# SterownikDriver_01.net
KiCad netlist of a schematic drawn in EAGLE
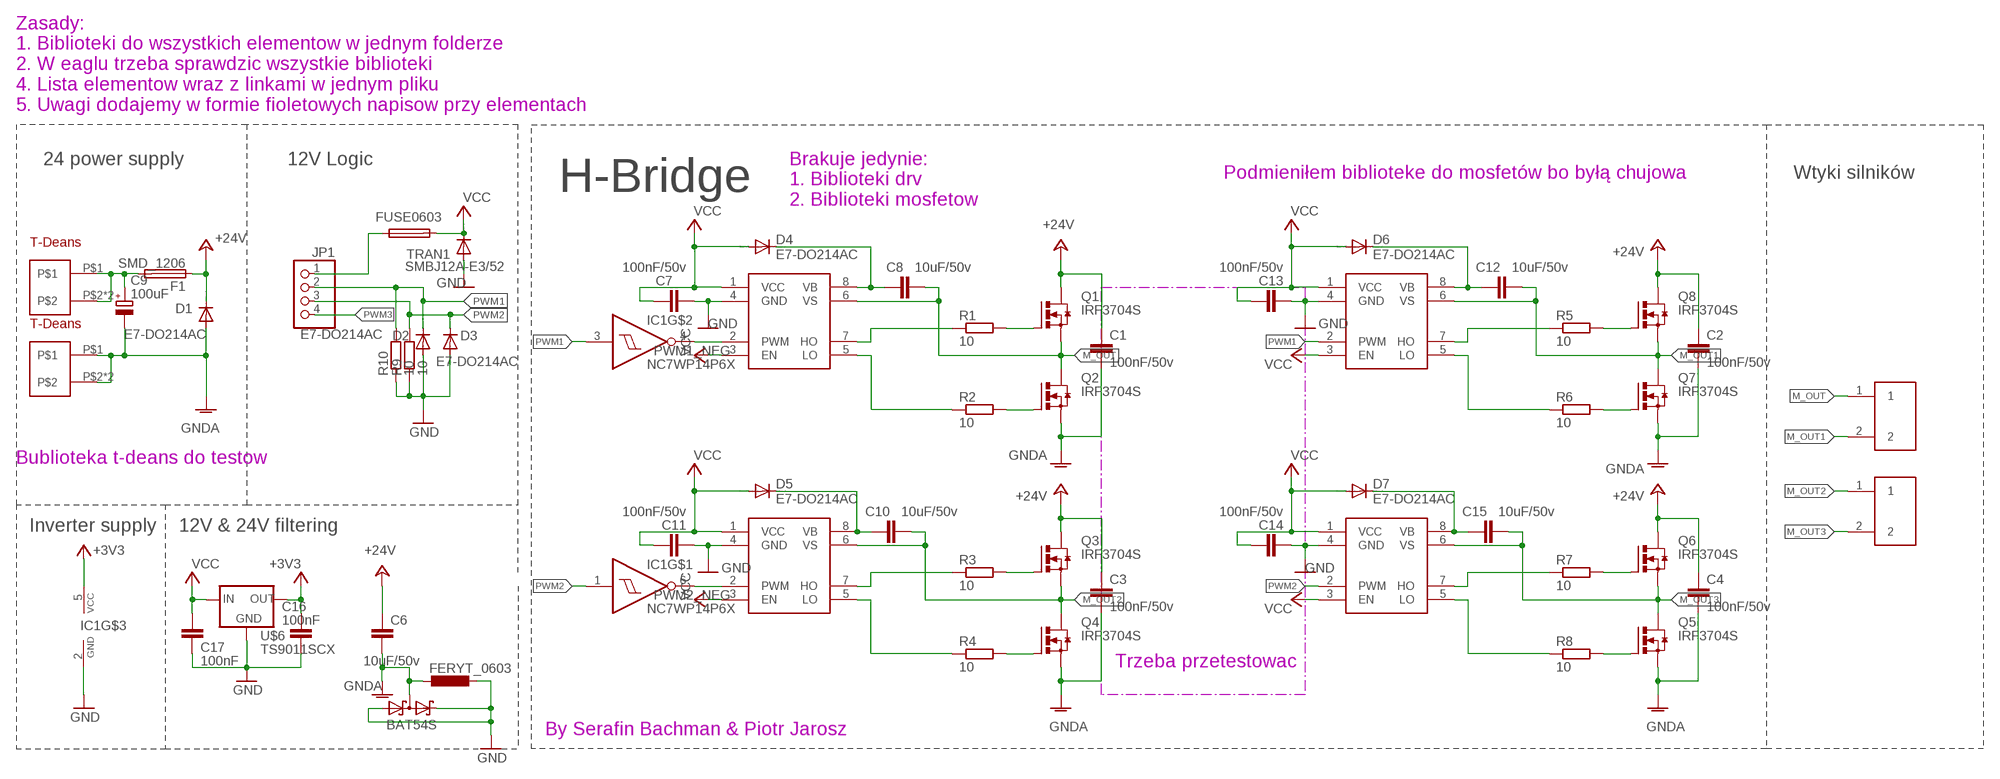
[diagram p0: schematic, sheet 1]

(export (version "E")
  (design (tool "Eeschema 10.0.6"))
  (components
    (comp (ref "C1")
      (value "100nF/50v")
      (footprint "eagle-import:C0603K")
      (libsource (lib "eagle-import") (part "C-EUC0603K"))
    )
    (comp (ref "C2")
      (value "100nF/50v")
      (footprint "eagle-import:C0603K")
      (libsource (lib "eagle-import") (part "C-EUC0603K"))
    )
    (comp (ref "C3")
      (value "100nF/50v")
      (footprint "eagle-import:C0603K")
      (libsource (lib "eagle-import") (part "C-EUC0603K"))
    )
    (comp (ref "C4")
      (value "100nF/50v")
      (footprint "eagle-import:C0603K")
      (libsource (lib "eagle-import") (part "C-EUC0603K"))
    )
    (comp (ref "C6")
      (value "10uF/50v")
      (footprint "eagle-import:C0603K")
      (libsource (lib "eagle-import") (part "C-EUC0603K"))
    )
    (comp (ref "C7")
      (value "100nF/50v")
      (footprint "eagle-import:C0603K")
      (libsource (lib "eagle-import") (part "C-EUC0603K"))
    )
    (comp (ref "C8")
      (value "10uF/50v")
      (footprint "eagle-import:C0603K")
      (libsource (lib "eagle-import") (part "C-EUC0603K"))
    )
    (comp (ref "C9")
      (value "100uF")
      (footprint "eagle-import:140CLH-0810")
      (libsource (lib "eagle-import") (part "CPOL-EU140CLH-0810"))
    )
    (comp (ref "C10")
      (value "10uF/50v")
      (footprint "eagle-import:C0603K")
      (libsource (lib "eagle-import") (part "C-EUC0603K"))
    )
    (comp (ref "C11")
      (value "100nF/50v")
      (footprint "eagle-import:C0603K")
      (libsource (lib "eagle-import") (part "C-EUC0603K"))
    )
    (comp (ref "C12")
      (value "10uF/50v")
      (footprint "eagle-import:C0603K")
      (libsource (lib "eagle-import") (part "C-EUC0603K"))
    )
    (comp (ref "C13")
      (value "100nF/50v")
      (footprint "eagle-import:C0603K")
      (libsource (lib "eagle-import") (part "C-EUC0603K"))
    )
    (comp (ref "C14")
      (value "100nF/50v")
      (footprint "eagle-import:C0603K")
      (libsource (lib "eagle-import") (part "C-EUC0603K"))
    )
    (comp (ref "C15")
      (value "10uF/50v")
      (footprint "eagle-import:C0603K")
      (libsource (lib "eagle-import") (part "C-EUC0603K"))
    )
    (comp (ref "C16")
      (value "100nF")
      (footprint "eagle-import:C0603K")
      (libsource (lib "eagle-import") (part "C-EUC0603K"))
    )
    (comp (ref "C17")
      (value "100nF")
      (footprint "eagle-import:C0603K")
      (libsource (lib "eagle-import") (part "C-EUC0603K"))
    )
    (comp (ref "D1")
      (value "E7-DO214AC")
      (footprint "eagle-import:DO214AC")
      (libsource (lib "eagle-import") (part "E7-DO214AC"))
    )
    (comp (ref "D2")
      (value "E7-DO214AC")
      (footprint "eagle-import:DO214AC")
      (libsource (lib "eagle-import") (part "E7-DO214AC"))
    )
    (comp (ref "D3")
      (value "E7-DO214AC")
      (footprint "eagle-import:DO214AC")
      (libsource (lib "eagle-import") (part "E7-DO214AC"))
    )
    (comp (ref "D4")
      (value "E7-DO214AC")
      (footprint "eagle-import:DO214AC")
      (libsource (lib "eagle-import") (part "E7-DO214AC"))
    )
    (comp (ref "D5")
      (value "E7-DO214AC")
      (footprint "eagle-import:DO214AC")
      (libsource (lib "eagle-import") (part "E7-DO214AC"))
    )
    (comp (ref "D6")
      (value "E7-DO214AC")
      (footprint "eagle-import:DO214AC")
      (libsource (lib "eagle-import") (part "E7-DO214AC"))
    )
    (comp (ref "D7")
      (value "E7-DO214AC")
      (footprint "eagle-import:DO214AC")
      (libsource (lib "eagle-import") (part "E7-DO214AC"))
    )
    (comp (ref "D8")
      (value "BAT54S")
      (footprint "eagle-import:SOT23")
      (libsource (lib "eagle-import") (part "BAT54S"))
    )
    (comp (ref "F1")
      (value "SMD_1206")
      (footprint "eagle-import:1026")
      (libsource (lib "eagle-import") (part "SMD_1206"))
    )
    (comp (ref "GND")
      (value "T-DEANS")
      (footprint "eagle-import:T-DEANS")
      (libsource (lib "eagle-import") (part "T-DEANS"))
    )
    (comp (ref "IC1")
      (value "NC7WP14P6X")
      (footprint "eagle-import:SOT65P210X110-6AN_SC88_SC70-6")
      (libsource (lib "eagle-import") (part "NC7W14P6XP"))
    )
    (comp (ref "JP1")
      (value "PINHD-1X4")
      (footprint "eagle-import:1X04")
      (libsource (lib "eagle-import") (part "PINHD-1X4"))
    )
    (comp (ref "Q1")
      (value "IRF3704S")
      (footprint "eagle-import:D2PACK")
      (libsource (lib "eagle-import") (part "IRF3704S"))
    )
    (comp (ref "Q2")
      (value "IRF3704S")
      (footprint "eagle-import:D2PACK")
      (libsource (lib "eagle-import") (part "IRF3704S"))
    )
    (comp (ref "Q3")
      (value "IRF3704S")
      (footprint "eagle-import:D2PACK")
      (libsource (lib "eagle-import") (part "IRF3704S"))
    )
    (comp (ref "Q4")
      (value "IRF3704S")
      (footprint "eagle-import:D2PACK")
      (libsource (lib "eagle-import") (part "IRF3704S"))
    )
    (comp (ref "Q5")
      (value "IRF3704S")
      (footprint "eagle-import:D2PACK")
      (libsource (lib "eagle-import") (part "IRF3704S"))
    )
    (comp (ref "Q6")
      (value "IRF3704S")
      (footprint "eagle-import:D2PACK")
      (libsource (lib "eagle-import") (part "IRF3704S"))
    )
    (comp (ref "Q7")
      (value "IRF3704S")
      (footprint "eagle-import:D2PACK")
      (libsource (lib "eagle-import") (part "IRF3704S"))
    )
    (comp (ref "Q8")
      (value "IRF3704S")
      (footprint "eagle-import:D2PACK")
      (libsource (lib "eagle-import") (part "IRF3704S"))
    )
    (comp (ref "R1")
      (value "10")
      (footprint "eagle-import:R0603")
      (libsource (lib "eagle-import") (part "R-EU_R0603"))
    )
    (comp (ref "R2")
      (value "10")
      (footprint "eagle-import:R0603")
      (libsource (lib "eagle-import") (part "R-EU_R0603"))
    )
    (comp (ref "R3")
      (value "10")
      (footprint "eagle-import:R0603")
      (libsource (lib "eagle-import") (part "R-EU_R0603"))
    )
    (comp (ref "R4")
      (value "10")
      (footprint "eagle-import:R0603")
      (libsource (lib "eagle-import") (part "R-EU_R0603"))
    )
    (comp (ref "R5")
      (value "10")
      (footprint "eagle-import:R0603")
      (libsource (lib "eagle-import") (part "R-EU_R0603"))
    )
    (comp (ref "R6")
      (value "10")
      (footprint "eagle-import:R0603")
      (libsource (lib "eagle-import") (part "R-EU_R0603"))
    )
    (comp (ref "R7")
      (value "10")
      (footprint "eagle-import:R0603")
      (libsource (lib "eagle-import") (part "R-EU_R0603"))
    )
    (comp (ref "R8")
      (value "10")
      (footprint "eagle-import:R0603")
      (libsource (lib "eagle-import") (part "R-EU_R0603"))
    )
    (comp (ref "R9")
      (value "10")
      (footprint "eagle-import:R0603")
      (libsource (lib "eagle-import") (part "R-EU_R0603"))
    )
    (comp (ref "R10")
      (value "10")
      (footprint "eagle-import:R0603")
      (libsource (lib "eagle-import") (part "R-EU_R0603"))
    )
    (comp (ref "TRAN1")
      (value "SMBJ12A-E3/52")
      (footprint "eagle-import:DO214AA")
      (libsource (lib "eagle-import") (part "SMBJ12A-E3/52"))
    )
    (comp (ref "U$3")
      (value "FUSE0603")
      (footprint "eagle-import:0603")
      (libsource (lib "eagle-import") (part "FUSE0603"))
    )
    (comp (ref "U$4")
      (value "FERYT_0603")
      (footprint "eagle-import:R0603")
      (libsource (lib "eagle-import") (part "FERYT_0603"))
    )
    (comp (ref "U$6")
      (value "TS9011SCX")
      (footprint "eagle-import:SOT23")
      (libsource (lib "eagle-import") (part "TS9011SCX"))
    )
    (comp (ref "U$7")
      (value "PTB-02_5.08MM")
      (footprint "eagle-import:PTB-5.08MM-02")
      (libsource (lib "eagle-import") (part "PTB-02_5.08MM"))
    )
    (comp (ref "U$9")
      (value "PTB-02_5.08MM")
      (footprint "eagle-import:PTB-5.08MM-02")
      (libsource (lib "eagle-import") (part "PTB-02_5.08MM"))
    )
    (comp (ref "U1")
      (value "IR2104")
      (footprint "eagle-import:SO08")
      (libsource (lib "eagle-import") (part "IR2104"))
    )
    (comp (ref "U2")
      (value "IR2104")
      (footprint "eagle-import:SO08")
      (libsource (lib "eagle-import") (part "IR2104"))
    )
    (comp (ref "U3")
      (value "IR2104")
      (footprint "eagle-import:SO08")
      (libsource (lib "eagle-import") (part "IR2104"))
    )
    (comp (ref "U4")
      (value "IR2104")
      (footprint "eagle-import:SO08")
      (libsource (lib "eagle-import") (part "IR2104"))
    )
    (comp (ref "VCC")
      (value "T-DEANS")
      (footprint "eagle-import:T-DEANS")
      (libsource (lib "eagle-import") (part "T-DEANS"))
    )
  )
  (nets
    (net (code "1") (name "+3V3") (class "Default")
      (node (ref "C16") (pin "1") (pinfunction "1_1") (pintype "passive"))
      (node (ref "IC1") (pin "5") (pinfunction "VCC_5") (pintype "power_in"))
      (node (ref "U$6") (pin "2") (pinfunction "OUT_2") (pintype "passive"))
    )
    (net (code "2") (name "+24V") (class "Default")
      (node (ref "C1") (pin "1") (pinfunction "1_1") (pintype "passive"))
      (node (ref "C2") (pin "1") (pinfunction "1_1") (pintype "passive"))
      (node (ref "C3") (pin "1") (pinfunction "1_1") (pintype "passive"))
      (node (ref "C4") (pin "1") (pinfunction "1_1") (pintype "passive"))
      (node (ref "C6") (pin "1") (pinfunction "1_1") (pintype "passive"))
      (node (ref "D1") (pin "C") (pinfunction "C_C") (pintype "passive"))
      (node (ref "F1") (pin "P$1") (pinfunction "1_P$1") (pintype "passive"))
      (node (ref "Q1") (pin "2") (pinfunction "D_2") (pintype "passive"))
      (node (ref "Q3") (pin "2") (pinfunction "D_2") (pintype "passive"))
      (node (ref "Q6") (pin "2") (pinfunction "D_2") (pintype "passive"))
      (node (ref "Q8") (pin "2") (pinfunction "D_2") (pintype "passive"))
    )
    (net (code "3") (name "/PWM1_NEG") (class "Default")
      (node (ref "IC1") (pin "4") (pinfunction "O_4") (pintype "output"))
      (node (ref "U1") (pin "2") (pinfunction "PWM_2") (pintype "input"))
    )
    (net (code "4") (name "/PWM2_NEG") (class "Default")
      (node (ref "IC1") (pin "6") (pinfunction "O_6") (pintype "output"))
      (node (ref "U3") (pin "2") (pinfunction "PWM_2") (pintype "input"))
    )
    (net (code "5") (name "GND") (class "Default")
      (node (ref "C11") (pin "2") (pinfunction "2_2") (pintype "passive"))
      (node (ref "C13") (pin "2") (pinfunction "2_2") (pintype "passive"))
      (node (ref "C14") (pin "2") (pinfunction "2_2") (pintype "passive"))
      (node (ref "C16") (pin "2") (pinfunction "2_2") (pintype "passive"))
      (node (ref "C17") (pin "2") (pinfunction "2_2") (pintype "passive"))
      (node (ref "C7") (pin "2") (pinfunction "2_2") (pintype "passive"))
      (node (ref "D2") (pin "A") (pinfunction "A_A") (pintype "passive"))
      (node (ref "D3") (pin "A") (pinfunction "A_A") (pintype "passive"))
      (node (ref "D8") (pin "1") (pinfunction "A1_1") (pintype "passive"))
      (node (ref "D8") (pin "2") (pinfunction "C2_2") (pintype "passive"))
      (node (ref "IC1") (pin "2") (pinfunction "GND_2") (pintype "power_in"))
      (node (ref "R10") (pin "1") (pinfunction "1_1") (pintype "passive"))
      (node (ref "R9") (pin "1") (pinfunction "1_1") (pintype "passive"))
      (node (ref "TRAN1") (pin "A") (pinfunction "A_A") (pintype "passive"))
      (node (ref "U$4") (pin "2") (pinfunction "2_2") (pintype "passive"))
      (node (ref "U$6") (pin "1") (pinfunction "GND_1") (pintype "input"))
      (node (ref "U1") (pin "4") (pinfunction "GND_4") (pintype "passive"))
      (node (ref "U2") (pin "4") (pinfunction "GND_4") (pintype "passive"))
      (node (ref "U3") (pin "4") (pinfunction "GND_4") (pintype "passive"))
      (node (ref "U4") (pin "4") (pinfunction "GND_4") (pintype "passive"))
    )
    (net (code "6") (name "GNDA") (class "Default")
      (node (ref "C1") (pin "2") (pinfunction "2_2") (pintype "passive"))
      (node (ref "C2") (pin "2") (pinfunction "2_2") (pintype "passive"))
      (node (ref "C3") (pin "2") (pinfunction "2_2") (pintype "passive"))
      (node (ref "C4") (pin "2") (pinfunction "2_2") (pintype "passive"))
      (node (ref "C6") (pin "2") (pinfunction "2_2") (pintype "passive"))
      (node (ref "C9") (pin "-") (pinfunction "-_-") (pintype "passive"))
      (node (ref "D1") (pin "A") (pinfunction "A_A") (pintype "passive"))
      (node (ref "D8") (pin "3") (pinfunction "C1A2_3") (pintype "passive"))
      (node (ref "GND") (pin "P$1") (pinfunction "P$1_P$1") (pintype "bidirectional"))
      (node (ref "GND") (pin "P$2") (pinfunction "P$2_P$2") (pintype "bidirectional"))
      (node (ref "GND") (pin "P$3") (pinfunction "P$2_P$3") (pintype "bidirectional"))
      (node (ref "Q2") (pin "3") (pinfunction "S_3") (pintype "passive"))
      (node (ref "Q4") (pin "3") (pinfunction "S_3") (pintype "passive"))
      (node (ref "Q5") (pin "3") (pinfunction "S_3") (pintype "passive"))
      (node (ref "Q7") (pin "3") (pinfunction "S_3") (pintype "passive"))
      (node (ref "U$4") (pin "1") (pinfunction "1_1") (pintype "passive"))
    )
    (net (code "7") (name "M_OUT") (class "Default")
      (node (ref "C8") (pin "2") (pinfunction "2_2") (pintype "passive"))
      (node (ref "Q1") (pin "3") (pinfunction "S_3") (pintype "passive"))
      (node (ref "Q2") (pin "2") (pinfunction "D_2") (pintype "passive"))
      (node (ref "U$7") (pin "1") (pinfunction "1_1") (pintype "bidirectional"))
      (node (ref "U1") (pin "6") (pinfunction "VS_6") (pintype "passive"))
    )
    (net (code "8") (name "M_OUT1") (class "Default")
      (node (ref "C12") (pin "2") (pinfunction "2_2") (pintype "passive"))
      (node (ref "Q7") (pin "2") (pinfunction "D_2") (pintype "passive"))
      (node (ref "Q8") (pin "3") (pinfunction "S_3") (pintype "passive"))
      (node (ref "U$7") (pin "2") (pinfunction "2_2") (pintype "bidirectional"))
      (node (ref "U2") (pin "6") (pinfunction "VS_6") (pintype "passive"))
    )
    (net (code "9") (name "M_OUT2") (class "Default")
      (node (ref "C10") (pin "2") (pinfunction "2_2") (pintype "passive"))
      (node (ref "Q3") (pin "3") (pinfunction "S_3") (pintype "passive"))
      (node (ref "Q4") (pin "2") (pinfunction "D_2") (pintype "passive"))
      (node (ref "U$9") (pin "1") (pinfunction "1_1") (pintype "bidirectional"))
      (node (ref "U3") (pin "6") (pinfunction "VS_6") (pintype "passive"))
    )
    (net (code "10") (name "M_OUT3") (class "Default")
      (node (ref "C15") (pin "2") (pinfunction "2_2") (pintype "passive"))
      (node (ref "Q5") (pin "2") (pinfunction "D_2") (pintype "passive"))
      (node (ref "Q6") (pin "3") (pinfunction "S_3") (pintype "passive"))
      (node (ref "U$9") (pin "2") (pinfunction "2_2") (pintype "bidirectional"))
      (node (ref "U4") (pin "6") (pinfunction "VS_6") (pintype "passive"))
    )
    (net (code "11") (name "Net-(F1-2)") (class "Default")
      (node (ref "C9") (pin "+") (pinfunction "+_+") (pintype "passive"))
      (node (ref "F1") (pin "P$2") (pinfunction "2_P$2") (pintype "passive"))
      (node (ref "VCC") (pin "P$1") (pinfunction "P$1_P$1") (pintype "bidirectional"))
      (node (ref "VCC") (pin "P$2") (pinfunction "P$2_P$2") (pintype "bidirectional"))
      (node (ref "VCC") (pin "P$3") (pinfunction "P$2_P$3") (pintype "bidirectional"))
    )
    (net (code "12") (name "Net-(JP1-Pad1)") (class "Default")
      (node (ref "JP1") (pin "1") (pinfunction "1_1") (pintype "passive"))
      (node (ref "U$3") (pin "1") (pinfunction "1_1") (pintype "passive"))
    )
    (net (code "13") (name "Net-(Q1-G)") (class "Default")
      (node (ref "Q1") (pin "1") (pinfunction "G_1") (pintype "passive"))
      (node (ref "R1") (pin "2") (pinfunction "2_2") (pintype "passive"))
    )
    (net (code "14") (name "Net-(Q2-G)") (class "Default")
      (node (ref "Q2") (pin "1") (pinfunction "G_1") (pintype "passive"))
      (node (ref "R2") (pin "2") (pinfunction "2_2") (pintype "passive"))
    )
    (net (code "15") (name "Net-(Q3-G)") (class "Default")
      (node (ref "Q3") (pin "1") (pinfunction "G_1") (pintype "passive"))
      (node (ref "R3") (pin "2") (pinfunction "2_2") (pintype "passive"))
    )
    (net (code "16") (name "Net-(Q4-G)") (class "Default")
      (node (ref "Q4") (pin "1") (pinfunction "G_1") (pintype "passive"))
      (node (ref "R4") (pin "2") (pinfunction "2_2") (pintype "passive"))
    )
    (net (code "17") (name "Net-(Q5-G)") (class "Default")
      (node (ref "Q5") (pin "1") (pinfunction "G_1") (pintype "passive"))
      (node (ref "R8") (pin "2") (pinfunction "2_2") (pintype "passive"))
    )
    (net (code "18") (name "Net-(Q6-G)") (class "Default")
      (node (ref "Q6") (pin "1") (pinfunction "G_1") (pintype "passive"))
      (node (ref "R7") (pin "2") (pinfunction "2_2") (pintype "passive"))
    )
    (net (code "19") (name "Net-(Q7-G)") (class "Default")
      (node (ref "Q7") (pin "1") (pinfunction "G_1") (pintype "passive"))
      (node (ref "R6") (pin "2") (pinfunction "2_2") (pintype "passive"))
    )
    (net (code "20") (name "Net-(Q8-G)") (class "Default")
      (node (ref "Q8") (pin "1") (pinfunction "G_1") (pintype "passive"))
      (node (ref "R5") (pin "2") (pinfunction "2_2") (pintype "passive"))
    )
    (net (code "21") (name "Net-(U1-HO)") (class "Default")
      (node (ref "R1") (pin "1") (pinfunction "1_1") (pintype "passive"))
      (node (ref "U1") (pin "7") (pinfunction "HO_7") (pintype "output"))
    )
    (net (code "22") (name "Net-(U1-LO)") (class "Default")
      (node (ref "R2") (pin "1") (pinfunction "1_1") (pintype "passive"))
      (node (ref "U1") (pin "5") (pinfunction "LO_5") (pintype "output"))
    )
    (net (code "23") (name "Net-(U1-VB)") (class "Default")
      (node (ref "C8") (pin "1") (pinfunction "1_1") (pintype "passive"))
      (node (ref "D4") (pin "C") (pinfunction "C_C") (pintype "passive"))
      (node (ref "U1") (pin "8") (pinfunction "VB_8") (pintype "passive"))
    )
    (net (code "24") (name "Net-(U2-HO)") (class "Default")
      (node (ref "R5") (pin "1") (pinfunction "1_1") (pintype "passive"))
      (node (ref "U2") (pin "7") (pinfunction "HO_7") (pintype "output"))
    )
    (net (code "25") (name "Net-(U2-LO)") (class "Default")
      (node (ref "R6") (pin "1") (pinfunction "1_1") (pintype "passive"))
      (node (ref "U2") (pin "5") (pinfunction "LO_5") (pintype "output"))
    )
    (net (code "26") (name "Net-(U2-VB)") (class "Default")
      (node (ref "C12") (pin "1") (pinfunction "1_1") (pintype "passive"))
      (node (ref "D6") (pin "C") (pinfunction "C_C") (pintype "passive"))
      (node (ref "U2") (pin "8") (pinfunction "VB_8") (pintype "passive"))
    )
    (net (code "27") (name "Net-(U3-HO)") (class "Default")
      (node (ref "R3") (pin "1") (pinfunction "1_1") (pintype "passive"))
      (node (ref "U3") (pin "7") (pinfunction "HO_7") (pintype "output"))
    )
    (net (code "28") (name "Net-(U3-LO)") (class "Default")
      (node (ref "R4") (pin "1") (pinfunction "1_1") (pintype "passive"))
      (node (ref "U3") (pin "5") (pinfunction "LO_5") (pintype "output"))
    )
    (net (code "29") (name "Net-(U3-VB)") (class "Default")
      (node (ref "C10") (pin "1") (pinfunction "1_1") (pintype "passive"))
      (node (ref "D5") (pin "C") (pinfunction "C_C") (pintype "passive"))
      (node (ref "U3") (pin "8") (pinfunction "VB_8") (pintype "passive"))
    )
    (net (code "30") (name "Net-(U4-HO)") (class "Default")
      (node (ref "R7") (pin "1") (pinfunction "1_1") (pintype "passive"))
      (node (ref "U4") (pin "7") (pinfunction "HO_7") (pintype "output"))
    )
    (net (code "31") (name "Net-(U4-LO)") (class "Default")
      (node (ref "R8") (pin "1") (pinfunction "1_1") (pintype "passive"))
      (node (ref "U4") (pin "5") (pinfunction "LO_5") (pintype "output"))
    )
    (net (code "32") (name "Net-(U4-VB)") (class "Default")
      (node (ref "C15") (pin "1") (pinfunction "1_1") (pintype "passive"))
      (node (ref "D7") (pin "C") (pinfunction "C_C") (pintype "passive"))
      (node (ref "U4") (pin "8") (pinfunction "VB_8") (pintype "passive"))
    )
    (net (code "33") (name "PWM1") (class "Default")
      (node (ref "D2") (pin "C") (pinfunction "C_C") (pintype "passive"))
      (node (ref "IC1") (pin "3") (pinfunction "I_3") (pintype "input"))
      (node (ref "JP1") (pin "2") (pinfunction "2_2") (pintype "passive"))
      (node (ref "R10") (pin "2") (pinfunction "2_2") (pintype "passive"))
      (node (ref "U2") (pin "2") (pinfunction "PWM_2") (pintype "input"))
    )
    (net (code "34") (name "PWM2") (class "Default")
      (node (ref "D3") (pin "C") (pinfunction "C_C") (pintype "passive"))
      (node (ref "IC1") (pin "1") (pinfunction "I_1") (pintype "input"))
      (node (ref "JP1") (pin "3") (pinfunction "3_3") (pintype "passive"))
      (node (ref "R9") (pin "2") (pinfunction "2_2") (pintype "passive"))
      (node (ref "U4") (pin "2") (pinfunction "PWM_2") (pintype "input"))
    )
    (net (code "35") (name "PWM3") (class "Default")
      (node (ref "JP1") (pin "4") (pinfunction "4_4") (pintype "passive"))
    )
    (net (code "36") (name "VCC") (class "Default")
      (node (ref "C11") (pin "1") (pinfunction "1_1") (pintype "passive"))
      (node (ref "C13") (pin "1") (pinfunction "1_1") (pintype "passive"))
      (node (ref "C14") (pin "1") (pinfunction "1_1") (pintype "passive"))
      (node (ref "C17") (pin "1") (pinfunction "1_1") (pintype "passive"))
      (node (ref "C7") (pin "1") (pinfunction "1_1") (pintype "passive"))
      (node (ref "D4") (pin "A") (pinfunction "A_A") (pintype "passive"))
      (node (ref "D5") (pin "A") (pinfunction "A_A") (pintype "passive"))
      (node (ref "D6") (pin "A") (pinfunction "A_A") (pintype "passive"))
      (node (ref "D7") (pin "A") (pinfunction "A_A") (pintype "passive"))
      (node (ref "TRAN1") (pin "C") (pinfunction "C_C") (pintype "passive"))
      (node (ref "U$3") (pin "2") (pinfunction "2_2") (pintype "passive"))
      (node (ref "U$6") (pin "3") (pinfunction "IN_3") (pintype "input"))
      (node (ref "U1") (pin "1") (pinfunction "VCC_1") (pintype "passive"))
      (node (ref "U1") (pin "3") (pinfunction "EN_3") (pintype "input"))
      (node (ref "U2") (pin "1") (pinfunction "VCC_1") (pintype "passive"))
      (node (ref "U2") (pin "3") (pinfunction "EN_3") (pintype "input"))
      (node (ref "U3") (pin "1") (pinfunction "VCC_1") (pintype "passive"))
      (node (ref "U3") (pin "3") (pinfunction "EN_3") (pintype "input"))
      (node (ref "U4") (pin "1") (pinfunction "VCC_1") (pintype "passive"))
      (node (ref "U4") (pin "3") (pinfunction "EN_3") (pintype "input"))
    )
  )
)
